# amp_nanopi.net
KiCad netlist of a schematic drawn in EAGLE
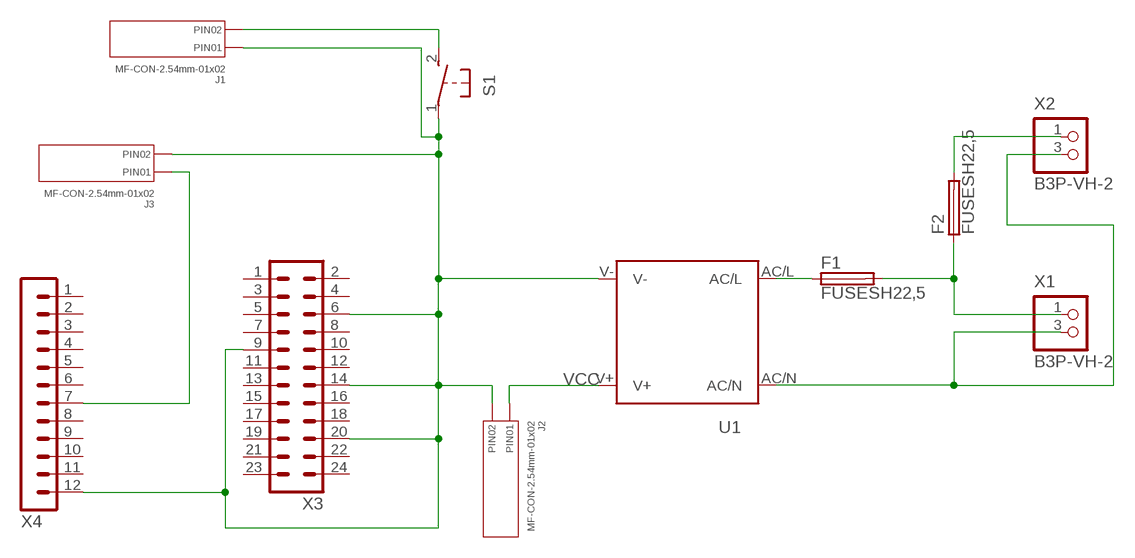
[diagram p0: schematic, sheet 1]

(export (version "E")
  (design (tool "Eeschema 10.0.6"))
  (components
    (comp (ref "F1")
      (value "FUSESH22,5")
      (footprint "eagle-import:SH22,5")
      (libsource (lib "eagle-import") (part "FUSESH22,5"))
    )
    (comp (ref "F2")
      (value "FUSESH22,5")
      (footprint "eagle-import:SH22,5")
      (libsource (lib "eagle-import") (part "FUSESH22,5"))
    )
    (comp (ref "J1")
      (value "MF-CON-2.54mm-01x02")
      (footprint "eagle-import:PTH_2.54MM_01X02")
      (fields (field (name "HOUSEPART") "YES"))
      (libsource (lib "eagle-import") (part "CON_01X02_PTH_2.54MM"))
    )
    (comp (ref "J2")
      (value "MF-CON-2.54mm-01x02")
      (footprint "eagle-import:PTH_2.54MM_01X02")
      (fields (field (name "HOUSEPART") "YES"))
      (libsource (lib "eagle-import") (part "CON_01X02_PTH_2.54MM"))
    )
    (comp (ref "J3")
      (value "MF-CON-2.54mm-01x02")
      (footprint "eagle-import:PTH_2.54MM_01X02")
      (fields (field (name "HOUSEPART") "YES"))
      (libsource (lib "eagle-import") (part "CON_01X02_PTH_2.54MM"))
    )
    (comp (ref "S1")
      (value "31-XX")
      (footprint "eagle-import:B3F-31XX")
      (fields (field (name "MPN") "B3F-3100"))
      (libsource (lib "eagle-import") (part "31-XX"))
    )
    (comp (ref "U1")
      (value "IRM_05/10")
      (footprint "eagle-import:IRM_05_10")
      (libsource (lib "eagle-import") (part "IRM_05/10"))
    )
    (comp (ref "X1")
      (value "B3P-VH-2")
      (footprint "eagle-import:B3P-VH-2")
      (libsource (lib "eagle-import") (part "B3P-VH-2"))
    )
    (comp (ref "X2")
      (value "B3P-VH-2")
      (footprint "eagle-import:B3P-VH-2")
      (libsource (lib "eagle-import") (part "B3P-VH-2"))
    )
    (comp (ref "X3")
      (value "MA12-2")
      (footprint "eagle-import:MA12-2")
      (libsource (lib "eagle-import") (part "MA12-2"))
    )
    (comp (ref "X4")
      (value "MA12-1")
      (footprint "eagle-import:MA12-1")
      (libsource (lib "eagle-import") (part "MA12-1"))
    )
  )
  (nets
    (net (code "1") (name "/VCC") (class "Default")
      (node (ref "J2") (pin "P$1") (pinfunction "PIN1_P$1") (pintype "bidirectional"))
      (node (ref "U1") (pin "V+") (pinfunction "V+_V+") (pintype "output"))
    )
    (net (code "2") (name "Net-(F1-Pad1)") (class "Default")
      (node (ref "F1") (pin "1") (pinfunction "1_1") (pintype "passive"))
      (node (ref "U1") (pin "AC/L") (pinfunction "AC/L_AC/L") (pintype "input"))
    )
    (net (code "3") (name "Net-(F1-Pad2)") (class "Default")
      (node (ref "F1") (pin "2") (pinfunction "2_2") (pintype "passive"))
      (node (ref "F2") (pin "1") (pinfunction "1_1") (pintype "passive"))
      (node (ref "X1") (pin "1") (pinfunction "1_1") (pintype "passive"))
    )
    (net (code "4") (name "Net-(F2-Pad2)") (class "Default")
      (node (ref "F2") (pin "2") (pinfunction "2_2") (pintype "passive"))
      (node (ref "X2") (pin "1") (pinfunction "1_1") (pintype "passive"))
    )
    (net (code "5") (name "Net-(J1-PIN1)") (class "Default")
      (node (ref "J1") (pin "P$1") (pinfunction "PIN1_P$1") (pintype "bidirectional"))
      (node (ref "J2") (pin "P$2") (pinfunction "PIN2_P$2") (pintype "bidirectional"))
      (node (ref "J3") (pin "P$2") (pinfunction "PIN2_P$2") (pintype "bidirectional"))
      (node (ref "S1") (pin "1") (pinfunction "P_1") (pintype "passive"))
      (node (ref "U1") (pin "V-") (pinfunction "V-_V-") (pintype "output"))
      (node (ref "X3") (pin "14") (pinfunction "14_14") (pintype "passive"))
      (node (ref "X3") (pin "20") (pinfunction "20_20") (pintype "passive"))
      (node (ref "X3") (pin "6") (pinfunction "6_6") (pintype "passive"))
      (node (ref "X3") (pin "9") (pinfunction "9_9") (pintype "passive"))
      (node (ref "X4") (pin "12") (pinfunction "12_12") (pintype "passive"))
    )
    (net (code "6") (name "Net-(J1-PIN2)") (class "Default")
      (node (ref "J1") (pin "P$2") (pinfunction "PIN2_P$2") (pintype "bidirectional"))
      (node (ref "S1") (pin "2") (pinfunction "S_2") (pintype "passive"))
    )
    (net (code "7") (name "Net-(J3-PIN1)") (class "Default")
      (node (ref "J3") (pin "P$1") (pinfunction "PIN1_P$1") (pintype "bidirectional"))
      (node (ref "X4") (pin "7") (pinfunction "7_7") (pintype "passive"))
    )
    (net (code "8") (name "Net-(X1-2)") (class "Default")
      (node (ref "U1") (pin "AC/N") (pinfunction "AC/N_AC/N") (pintype "input"))
      (node (ref "X1") (pin "3") (pinfunction "2_3") (pintype "passive"))
      (node (ref "X2") (pin "3") (pinfunction "2_3") (pintype "passive"))
    )
    (net (code "9") (name "unconnected-(X3-Pad1)") (class "Default")
      (node (ref "X3") (pin "1") (pinfunction "1_1") (pintype "passive"))
    )
    (net (code "10") (name "unconnected-(X3-Pad2)") (class "Default")
      (node (ref "X3") (pin "2") (pinfunction "2_2") (pintype "passive"))
    )
    (net (code "11") (name "unconnected-(X3-Pad3)") (class "Default")
      (node (ref "X3") (pin "3") (pinfunction "3_3") (pintype "passive"))
    )
    (net (code "12") (name "unconnected-(X3-Pad4)") (class "Default")
      (node (ref "X3") (pin "4") (pinfunction "4_4") (pintype "passive"))
    )
    (net (code "13") (name "unconnected-(X3-Pad5)") (class "Default")
      (node (ref "X3") (pin "5") (pinfunction "5_5") (pintype "passive"))
    )
    (net (code "14") (name "unconnected-(X3-Pad7)") (class "Default")
      (node (ref "X3") (pin "7") (pinfunction "7_7") (pintype "passive"))
    )
    (net (code "15") (name "unconnected-(X3-Pad8)") (class "Default")
      (node (ref "X3") (pin "8") (pinfunction "8_8") (pintype "passive"))
    )
    (net (code "16") (name "unconnected-(X3-Pad10)") (class "Default")
      (node (ref "X3") (pin "10") (pinfunction "10_10") (pintype "passive"))
    )
    (net (code "17") (name "unconnected-(X3-Pad11)") (class "Default")
      (node (ref "X3") (pin "11") (pinfunction "11_11") (pintype "passive"))
    )
    (net (code "18") (name "unconnected-(X3-Pad12)") (class "Default")
      (node (ref "X3") (pin "12") (pinfunction "12_12") (pintype "passive"))
    )
    (net (code "19") (name "unconnected-(X3-Pad13)") (class "Default")
      (node (ref "X3") (pin "13") (pinfunction "13_13") (pintype "passive"))
    )
    (net (code "20") (name "unconnected-(X3-Pad15)") (class "Default")
      (node (ref "X3") (pin "15") (pinfunction "15_15") (pintype "passive"))
    )
    (net (code "21") (name "unconnected-(X3-Pad16)") (class "Default")
      (node (ref "X3") (pin "16") (pinfunction "16_16") (pintype "passive"))
    )
    (net (code "22") (name "unconnected-(X3-Pad17)") (class "Default")
      (node (ref "X3") (pin "17") (pinfunction "17_17") (pintype "passive"))
    )
    (net (code "23") (name "unconnected-(X3-Pad18)") (class "Default")
      (node (ref "X3") (pin "18") (pinfunction "18_18") (pintype "passive"))
    )
    (net (code "24") (name "unconnected-(X3-Pad19)") (class "Default")
      (node (ref "X3") (pin "19") (pinfunction "19_19") (pintype "passive"))
    )
    (net (code "25") (name "unconnected-(X3-Pad21)") (class "Default")
      (node (ref "X3") (pin "21") (pinfunction "21_21") (pintype "passive"))
    )
    (net (code "26") (name "unconnected-(X3-Pad22)") (class "Default")
      (node (ref "X3") (pin "22") (pinfunction "22_22") (pintype "passive"))
    )
    (net (code "27") (name "unconnected-(X3-Pad23)") (class "Default")
      (node (ref "X3") (pin "23") (pinfunction "23_23") (pintype "passive"))
    )
    (net (code "28") (name "unconnected-(X3-Pad24)") (class "Default")
      (node (ref "X3") (pin "24") (pinfunction "24_24") (pintype "passive"))
    )
    (net (code "29") (name "unconnected-(X4-Pad1)") (class "Default")
      (node (ref "X4") (pin "1") (pinfunction "1_1") (pintype "passive"))
    )
    (net (code "30") (name "unconnected-(X4-Pad2)") (class "Default")
      (node (ref "X4") (pin "2") (pinfunction "2_2") (pintype "passive"))
    )
    (net (code "31") (name "unconnected-(X4-Pad3)") (class "Default")
      (node (ref "X4") (pin "3") (pinfunction "3_3") (pintype "passive"))
    )
    (net (code "32") (name "unconnected-(X4-Pad4)") (class "Default")
      (node (ref "X4") (pin "4") (pinfunction "4_4") (pintype "passive"))
    )
    (net (code "33") (name "unconnected-(X4-Pad5)") (class "Default")
      (node (ref "X4") (pin "5") (pinfunction "5_5") (pintype "passive"))
    )
    (net (code "34") (name "unconnected-(X4-Pad6)") (class "Default")
      (node (ref "X4") (pin "6") (pinfunction "6_6") (pintype "passive"))
    )
    (net (code "35") (name "unconnected-(X4-Pad8)") (class "Default")
      (node (ref "X4") (pin "8") (pinfunction "8_8") (pintype "passive"))
    )
    (net (code "36") (name "unconnected-(X4-Pad9)") (class "Default")
      (node (ref "X4") (pin "9") (pinfunction "9_9") (pintype "passive"))
    )
    (net (code "37") (name "unconnected-(X4-Pad10)") (class "Default")
      (node (ref "X4") (pin "10") (pinfunction "10_10") (pintype "passive"))
    )
    (net (code "38") (name "unconnected-(X4-Pad11)") (class "Default")
      (node (ref "X4") (pin "11") (pinfunction "11_11") (pintype "passive"))
    )
  )
)
